# driver.net
KiCad netlist of a schematic drawn in EAGLE
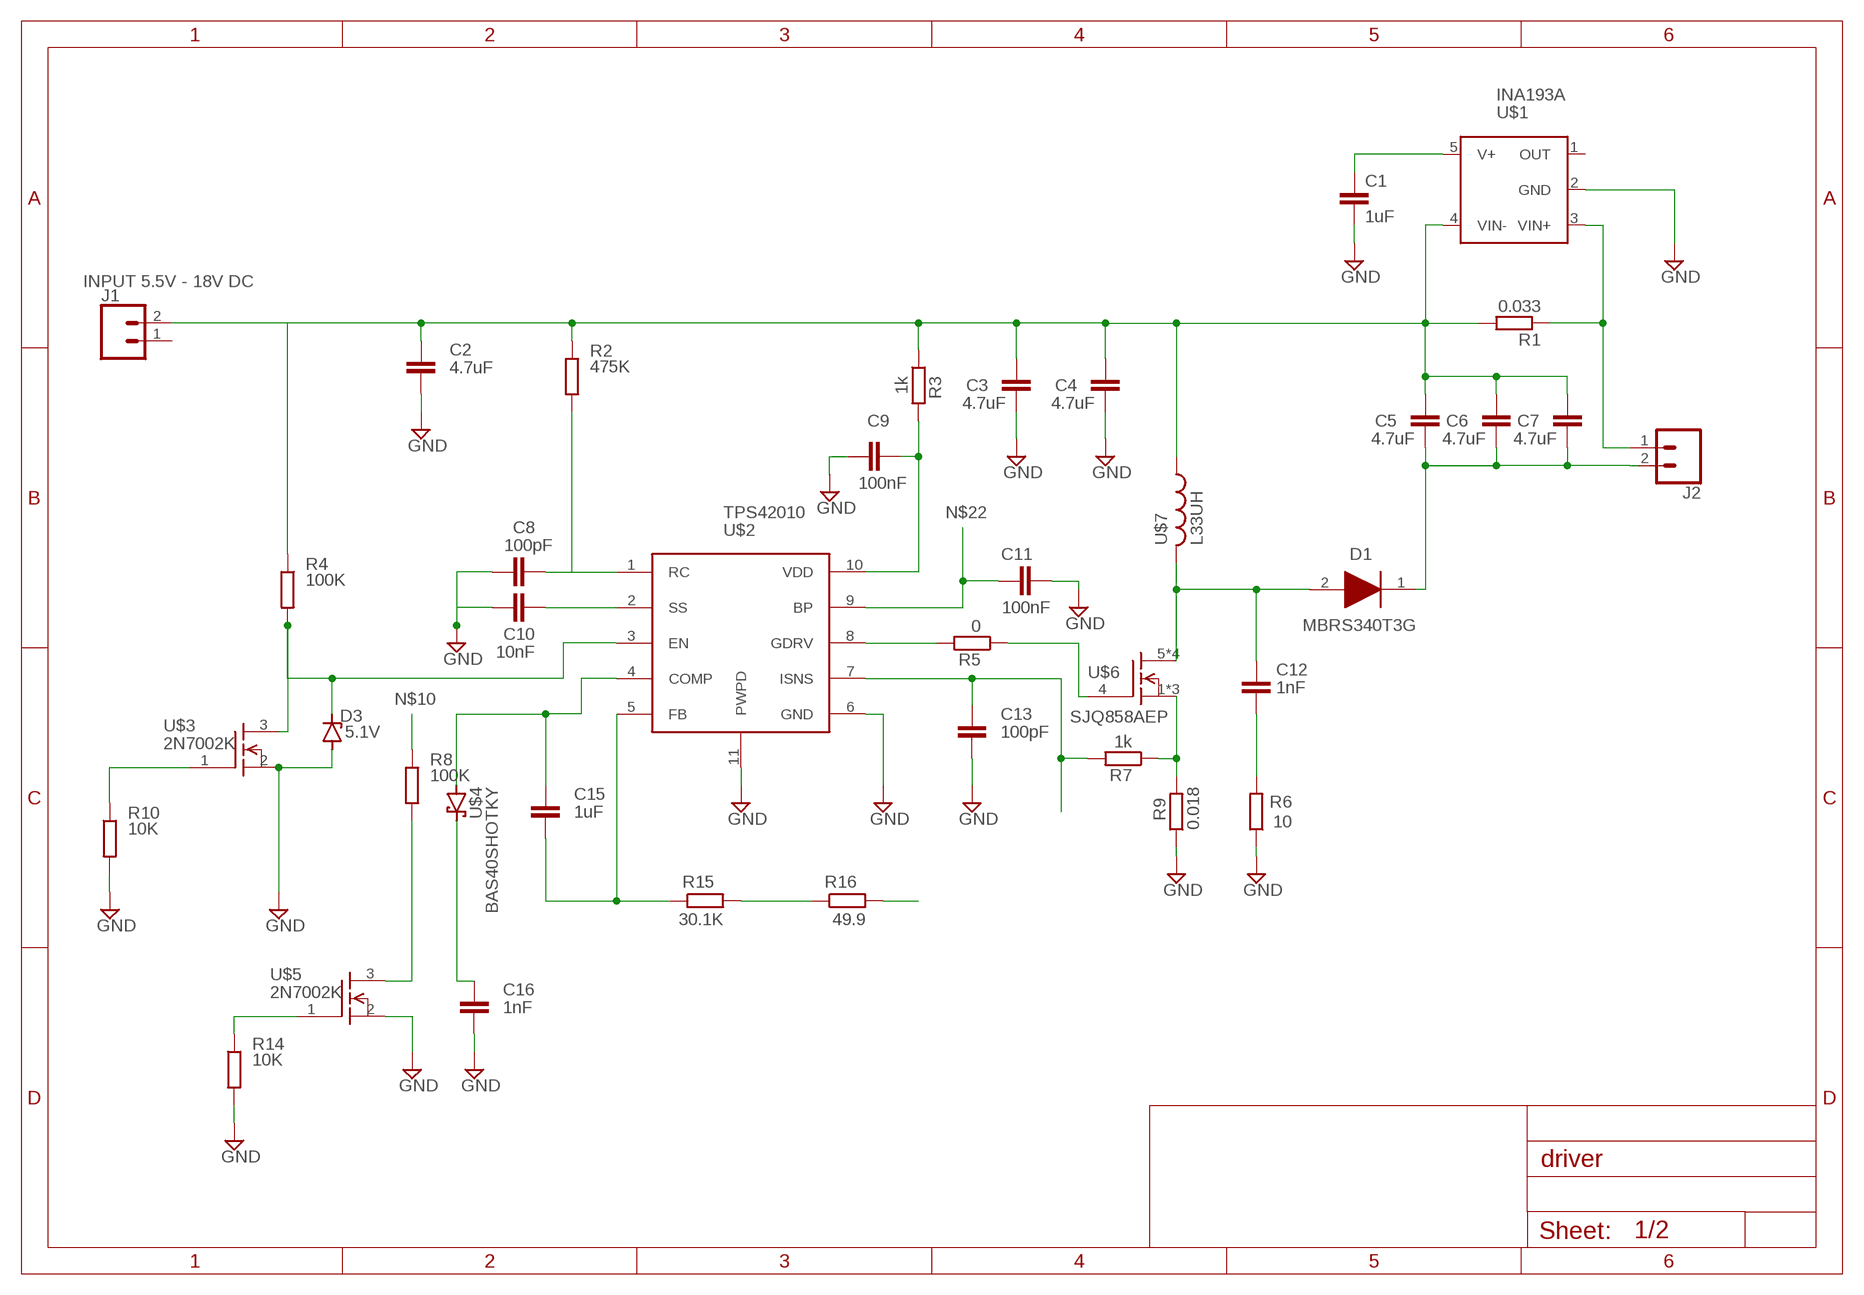
[diagram p0: schematic, sheet 1]
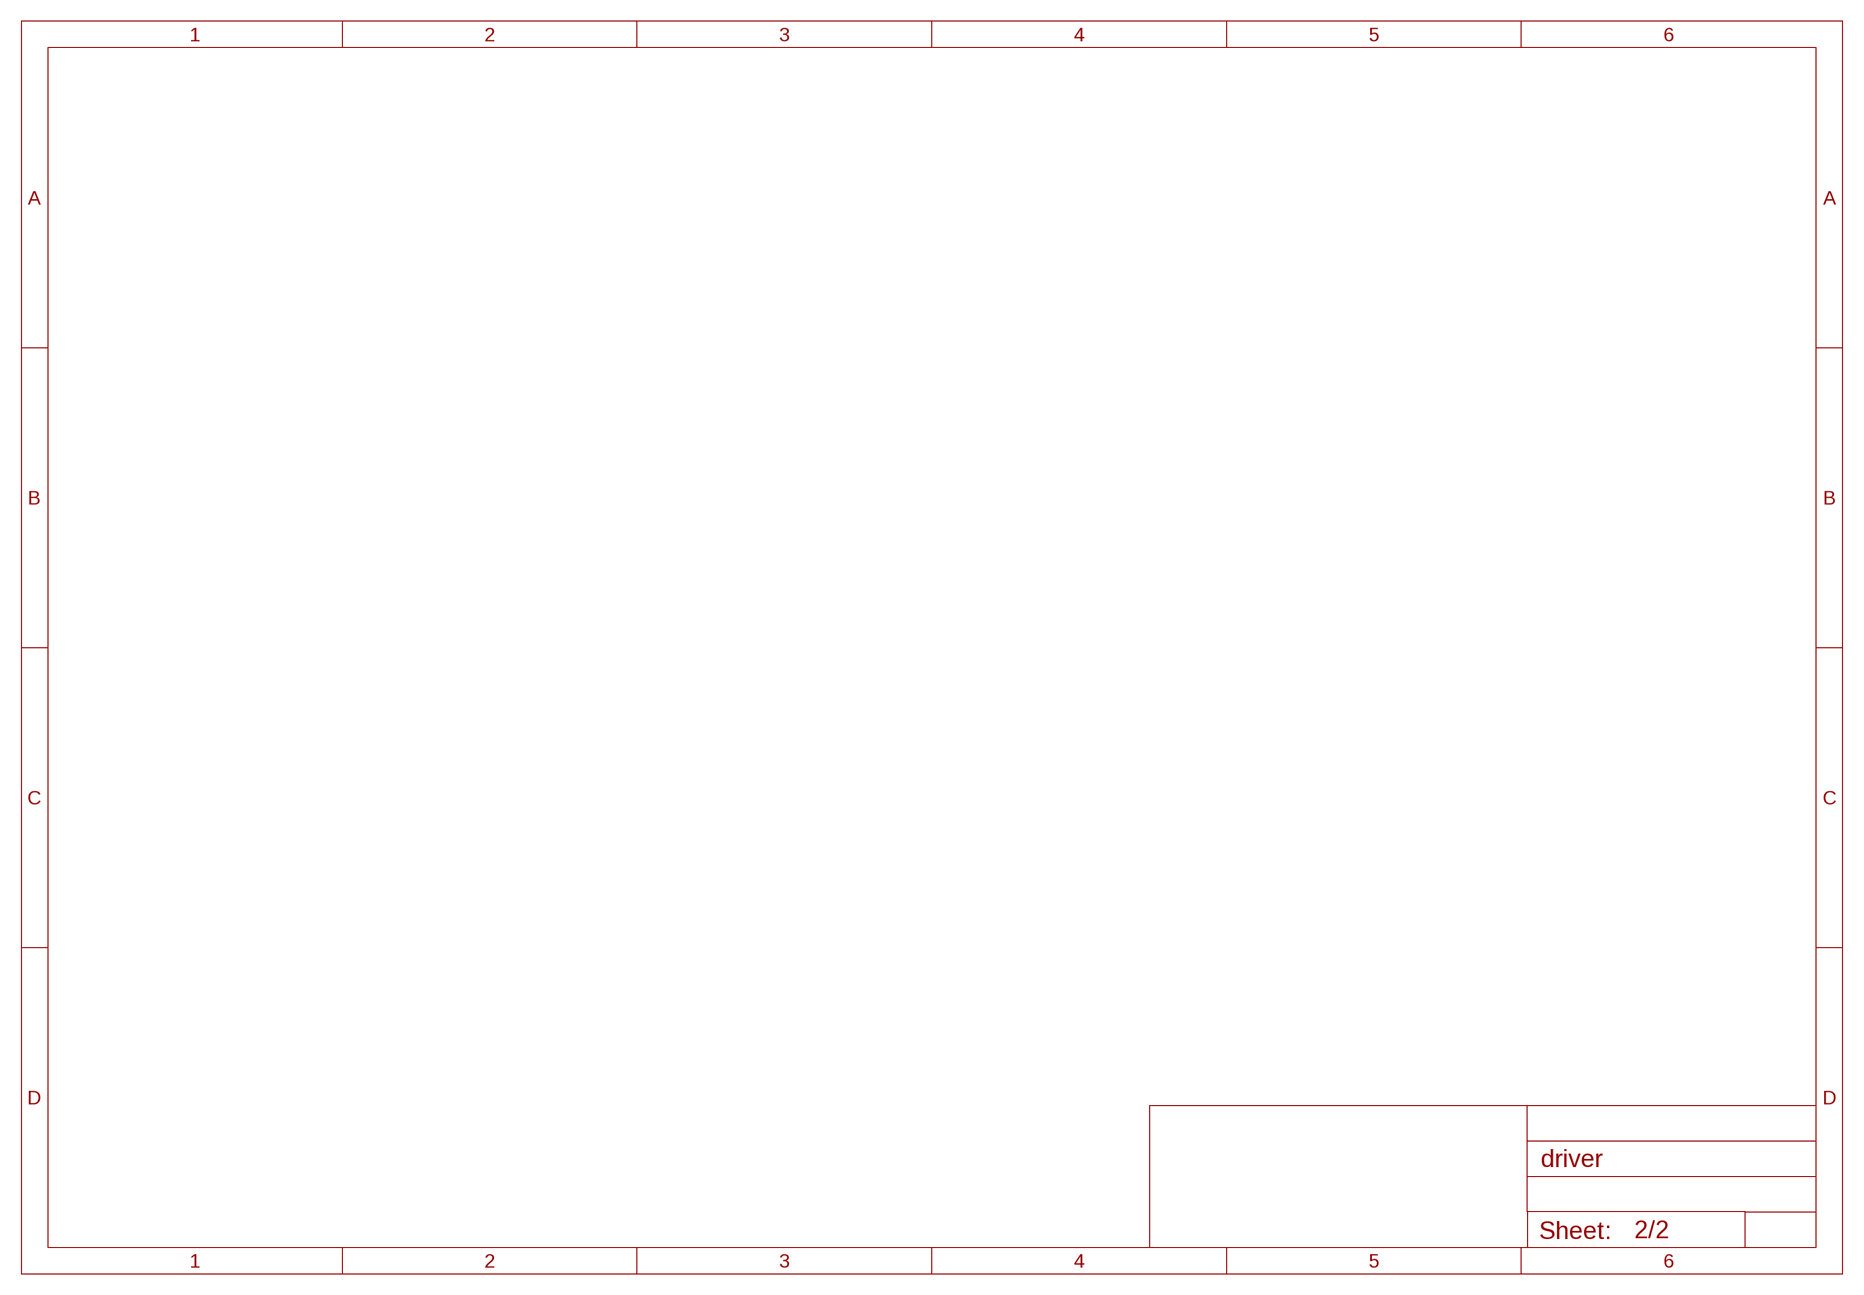
[diagram p1: schematic, sheet 2]

(export (version "E")
  (design (tool "Eeschema 10.0.6"))
  (components
    (comp (ref "C1")
      (value "1uF")
      (footprint "eagle-import:C0603")
      (libsource (lib "eagle-import") (part "C-EUC0603"))
    )
    (comp (ref "C2")
      (value "4.7uF")
      (footprint "eagle-import:C0603")
      (libsource (lib "eagle-import") (part "C-EUC0603"))
    )
    (comp (ref "C3")
      (value "4.7uF")
      (footprint "eagle-import:C0603")
      (libsource (lib "eagle-import") (part "C-EUC0603"))
    )
    (comp (ref "C4")
      (value "4.7uF")
      (footprint "eagle-import:C0603")
      (libsource (lib "eagle-import") (part "C-EUC0603"))
    )
    (comp (ref "C5")
      (value "4.7uF")
      (footprint "eagle-import:C0603")
      (libsource (lib "eagle-import") (part "C-EUC0603"))
    )
    (comp (ref "C6")
      (value "4.7uF")
      (footprint "eagle-import:C0603")
      (libsource (lib "eagle-import") (part "C-EUC0603"))
    )
    (comp (ref "C7")
      (value "4.7uF")
      (footprint "eagle-import:C0603")
      (libsource (lib "eagle-import") (part "C-EUC0603"))
    )
    (comp (ref "C8")
      (value "100pF")
      (footprint "eagle-import:C0603")
      (libsource (lib "eagle-import") (part "C-EUC0603"))
    )
    (comp (ref "C9")
      (value "100nF")
      (footprint "eagle-import:C0603")
      (libsource (lib "eagle-import") (part "C-EUC0603"))
    )
    (comp (ref "C10")
      (value "10nF")
      (footprint "eagle-import:C0603")
      (libsource (lib "eagle-import") (part "C-EUC0603"))
    )
    (comp (ref "C11")
      (value "100nF")
      (footprint "eagle-import:C0603")
      (libsource (lib "eagle-import") (part "C-EUC0603"))
    )
    (comp (ref "C12")
      (value "1nF")
      (footprint "eagle-import:C0603")
      (libsource (lib "eagle-import") (part "C-EUC0603"))
    )
    (comp (ref "C13")
      (value "100pF")
      (footprint "eagle-import:C0603")
      (libsource (lib "eagle-import") (part "C-EUC0603"))
    )
    (comp (ref "C15")
      (value "1uF")
      (footprint "eagle-import:C0603")
      (libsource (lib "eagle-import") (part "C-EUC0603"))
    )
    (comp (ref "C16")
      (value "1nF")
      (footprint "eagle-import:C0603")
      (libsource (lib "eagle-import") (part "C-EUC0603"))
    )
    (comp (ref "D1")
      (value "MBRS340T3G")
      (footprint "eagle-import:DIOM8059X261N")
      (fields (field (name "MOUSER_PART_NUMBER") "863-MBRS340T3G"))
      (libsource (lib "eagle-import") (part "MBRS340T3G"))
    )
    (comp (ref "D3")
      (value "5.1V")
      (footprint "eagle-import:SOT23")
      (libsource (lib "eagle-import") (part "ZENER-DIODESOT23"))
    )
    (comp (ref "J1")
      (value "CONN_02PTH4")
      (footprint "eagle-import:1X02_XTRA_BIG")
      (libsource (lib "eagle-import") (part "CONN_02PTH4"))
    )
    (comp (ref "J2")
      (value "CONN_02PTH4")
      (footprint "eagle-import:1X02_XTRA_BIG")
      (libsource (lib "eagle-import") (part "CONN_02PTH4"))
    )
    (comp (ref "R1")
      (value "0.033")
      (footprint "eagle-import:R0603")
      (libsource (lib "eagle-import") (part "rcl_334_R-EU_R0603"))
    )
    (comp (ref "R2")
      (value "475K")
      (footprint "eagle-import:R0603")
      (libsource (lib "eagle-import") (part "rcl_334_R-EU_R0603"))
    )
    (comp (ref "R3")
      (value "1k")
      (footprint "eagle-import:R0603")
      (libsource (lib "eagle-import") (part "rcl_334_R-EU_R0603"))
    )
    (comp (ref "R4")
      (value "100K")
      (footprint "eagle-import:R0603")
      (libsource (lib "eagle-import") (part "rcl_334_R-EU_R0603"))
    )
    (comp (ref "R5")
      (value "0")
      (footprint "eagle-import:R0603")
      (libsource (lib "eagle-import") (part "rcl_334_R-EU_R0603"))
    )
    (comp (ref "R6")
      (value "10")
      (footprint "eagle-import:R1206")
      (libsource (lib "eagle-import") (part "R-EU_R1206"))
    )
    (comp (ref "R7")
      (value "1k")
      (footprint "eagle-import:R0603")
      (libsource (lib "eagle-import") (part "rcl_334_R-EU_R0603"))
    )
    (comp (ref "R8")
      (value "100K")
      (footprint "eagle-import:R0603")
      (libsource (lib "eagle-import") (part "rcl_334_R-EU_R0603"))
    )
    (comp (ref "R9")
      (value "0.018")
      (footprint "eagle-import:R1206")
      (libsource (lib "eagle-import") (part "R-EU_R1206"))
    )
    (comp (ref "R10")
      (value "10K")
      (footprint "eagle-import:R0603")
      (libsource (lib "eagle-import") (part "rcl_334_R-EU_R0603"))
    )
    (comp (ref "R14")
      (value "10K")
      (footprint "eagle-import:R0603")
      (libsource (lib "eagle-import") (part "rcl_334_R-EU_R0603"))
    )
    (comp (ref "R15")
      (value "30.1K")
      (footprint "eagle-import:R0603")
      (libsource (lib "eagle-import") (part "rcl_334_R-EU_R0603"))
    )
    (comp (ref "R16")
      (value "49.9")
      (footprint "eagle-import:R0603")
      (libsource (lib "eagle-import") (part "rcl_334_R-EU_R0603"))
    )
    (comp (ref "U$1")
      (value "INA193A")
      (footprint "eagle-import:SOT95P280X145-5N")
      (libsource (lib "eagle-import") (part "INA193A"))
    )
    (comp (ref "U$2")
      (value "TPS42010")
      (footprint "eagle-import:SOP50P490X110-11N")
      (libsource (lib "eagle-import") (part "TPS42010"))
    )
    (comp (ref "U$3")
      (value "2N7002K")
      (footprint "eagle-import:SOT95P237X112-3N")
      (libsource (lib "eagle-import") (part "2N7002K"))
    )
    (comp (ref "U$4")
      (value "BAS40SHOTKY")
      (footprint "eagle-import:SOT323-3")
      (libsource (lib "eagle-import") (part "BAS40SHOTKY"))
    )
    (comp (ref "U$5")
      (value "2N7002K")
      (footprint "eagle-import:SOT95P237X112-3N")
      (libsource (lib "eagle-import") (part "2N7002K"))
    )
    (comp (ref "U$6")
      (value "SJQ858AEP")
      (footprint "eagle-import:SQJ858AEPT1_GE3")
      (libsource (lib "eagle-import") (part "SJQ858AEP"))
    )
    (comp (ref "U$7")
      (value "L33UH")
      (footprint "eagle-import:L33UH")
      (libsource (lib "eagle-import") (part "L33UH"))
    )
  )
  (nets
    (net (code "1") (name "GND") (class "Default")
      (node (ref "C1") (pin "2") (pinfunction "2_2") (pintype "passive"))
      (node (ref "C10") (pin "1") (pinfunction "1_1") (pintype "passive"))
      (node (ref "C11") (pin "2") (pinfunction "2_2") (pintype "passive"))
      (node (ref "C13") (pin "2") (pinfunction "2_2") (pintype "passive"))
      (node (ref "C16") (pin "2") (pinfunction "2_2") (pintype "passive"))
      (node (ref "C2") (pin "2") (pinfunction "2_2") (pintype "passive"))
      (node (ref "C3") (pin "2") (pinfunction "2_2") (pintype "passive"))
      (node (ref "C4") (pin "2") (pinfunction "2_2") (pintype "passive"))
      (node (ref "C8") (pin "1") (pinfunction "1_1") (pintype "passive"))
      (node (ref "C9") (pin "2") (pinfunction "2_2") (pintype "passive"))
      (node (ref "D3") (pin "1") (pinfunction "A_1") (pintype "passive"))
      (node (ref "R10") (pin "2") (pinfunction "2_2") (pintype "passive"))
      (node (ref "R14") (pin "2") (pinfunction "2_2") (pintype "passive"))
      (node (ref "R6") (pin "1") (pinfunction "1_1") (pintype "passive"))
      (node (ref "R9") (pin "1") (pinfunction "1_1") (pintype "passive"))
      (node (ref "U$1") (pin "2") (pinfunction "GND_2") (pintype "bidirectional"))
      (node (ref "U$2") (pin "11") (pinfunction "PWPD_11") (pintype "bidirectional"))
      (node (ref "U$2") (pin "6") (pinfunction "GND_6") (pintype "bidirectional"))
      (node (ref "U$3") (pin "2") (pinfunction "S_2") (pintype "bidirectional"))
      (node (ref "U$5") (pin "2") (pinfunction "S_2") (pintype "bidirectional"))
    )
    (net (code "2") (name "N$10") (class "Default")
      (node (ref "R8") (pin "1") (pinfunction "1_1") (pintype "passive"))
    )
    (net (code "3") (name "N$22") (class "Default")
      (node (ref "C11") (pin "1") (pinfunction "1_1") (pintype "passive"))
      (node (ref "U$2") (pin "9") (pinfunction "BP_9") (pintype "bidirectional"))
    )
    (net (code "4") (name "Net-(C12-Pad1)") (class "Default")
      (node (ref "C12") (pin "1") (pinfunction "1_1") (pintype "passive"))
      (node (ref "R6") (pin "2") (pinfunction "2_2") (pintype "passive"))
    )
    (net (code "5") (name "Net-(D1-A)") (class "Default")
      (node (ref "C12") (pin "2") (pinfunction "2_2") (pintype "passive"))
      (node (ref "D1") (pin "2") (pinfunction "A_2") (pintype "bidirectional"))
      (node (ref "U$6") (pin "5") (pinfunction "D_5") (pintype "bidirectional"))
      (node (ref "U$6") (pin "6") (pinfunction "D_6") (pintype "bidirectional"))
      (node (ref "U$6") (pin "7") (pinfunction "D_7") (pintype "bidirectional"))
      (node (ref "U$6") (pin "8") (pinfunction "D_8") (pintype "bidirectional"))
      (node (ref "U$7") (pin "P$2") (pinfunction "2_P$2") (pintype "passive"))
    )
    (net (code "6") (name "Net-(D1-K)") (class "Default")
      (node (ref "C5") (pin "2") (pinfunction "2_2") (pintype "passive"))
      (node (ref "C6") (pin "2") (pinfunction "2_2") (pintype "passive"))
      (node (ref "C7") (pin "2") (pinfunction "2_2") (pintype "passive"))
      (node (ref "D1") (pin "1") (pinfunction "K_1") (pintype "bidirectional"))
      (node (ref "J2") (pin "2") (pinfunction "2_2") (pintype "passive"))
    )
    (net (code "7") (name "Net-(D3-C)") (class "Default")
      (node (ref "D3") (pin "3") (pinfunction "C_3") (pintype "passive"))
      (node (ref "R4") (pin "2") (pinfunction "2_2") (pintype "passive"))
      (node (ref "U$2") (pin "3") (pinfunction "EN_3") (pintype "bidirectional"))
      (node (ref "U$3") (pin "3") (pinfunction "D_3") (pintype "bidirectional"))
    )
    (net (code "8") (name "Net-(R7-Pad1)") (class "Default")
      (node (ref "R7") (pin "1") (pinfunction "1_1") (pintype "passive"))
      (node (ref "R9") (pin "2") (pinfunction "2_2") (pintype "passive"))
      (node (ref "U$6") (pin "1") (pinfunction "S_1") (pintype "bidirectional"))
      (node (ref "U$6") (pin "2") (pinfunction "S_2") (pintype "bidirectional"))
      (node (ref "U$6") (pin "3") (pinfunction "S_3") (pintype "bidirectional"))
    )
    (net (code "9") (name "Net-(R15-Pad2)") (class "Default")
      (node (ref "R15") (pin "2") (pinfunction "2_2") (pintype "passive"))
      (node (ref "R16") (pin "1") (pinfunction "1_1") (pintype "passive"))
    )
    (net (code "10") (name "Net-(U$1-V+)") (class "Default")
      (node (ref "C1") (pin "1") (pinfunction "1_1") (pintype "passive"))
      (node (ref "U$1") (pin "5") (pinfunction "V+_5") (pintype "bidirectional"))
    )
    (net (code "11") (name "Net-(U$1-VIN+)") (class "Default")
      (node (ref "J2") (pin "1") (pinfunction "1_1") (pintype "passive"))
      (node (ref "R1") (pin "1") (pinfunction "1_1") (pintype "passive"))
      (node (ref "U$1") (pin "3") (pinfunction "VIN+_3") (pintype "bidirectional"))
    )
    (net (code "12") (name "Net-(U$1-VIN-)") (class "Default")
      (node (ref "C2") (pin "1") (pinfunction "1_1") (pintype "passive"))
      (node (ref "C3") (pin "1") (pinfunction "1_1") (pintype "passive"))
      (node (ref "C4") (pin "1") (pinfunction "1_1") (pintype "passive"))
      (node (ref "C5") (pin "1") (pinfunction "1_1") (pintype "passive"))
      (node (ref "C6") (pin "1") (pinfunction "1_1") (pintype "passive"))
      (node (ref "C7") (pin "1") (pinfunction "1_1") (pintype "passive"))
      (node (ref "J1") (pin "2") (pinfunction "2_2") (pintype "passive"))
      (node (ref "R1") (pin "2") (pinfunction "2_2") (pintype "passive"))
      (node (ref "R2") (pin "1") (pinfunction "1_1") (pintype "passive"))
      (node (ref "R3") (pin "1") (pinfunction "1_1") (pintype "passive"))
      (node (ref "R4") (pin "1") (pinfunction "1_1") (pintype "passive"))
      (node (ref "U$1") (pin "4") (pinfunction "VIN-_4") (pintype "bidirectional"))
      (node (ref "U$7") (pin "P$1") (pinfunction "1_P$1") (pintype "passive"))
    )
    (net (code "13") (name "Net-(U$2-COMP)") (class "Default")
      (node (ref "C15") (pin "1") (pinfunction "1_1") (pintype "passive"))
      (node (ref "U$2") (pin "4") (pinfunction "COMP_4") (pintype "bidirectional"))
      (node (ref "U$4") (pin "P$1") (pinfunction "A_P$1") (pintype "passive"))
    )
    (net (code "14") (name "Net-(U$2-FB)") (class "Default")
      (node (ref "C15") (pin "2") (pinfunction "2_2") (pintype "passive"))
      (node (ref "R15") (pin "1") (pinfunction "1_1") (pintype "passive"))
      (node (ref "U$2") (pin "5") (pinfunction "FB_5") (pintype "bidirectional"))
    )
    (net (code "15") (name "Net-(U$2-GDRV)") (class "Default")
      (node (ref "R5") (pin "2") (pinfunction "2_2") (pintype "passive"))
      (node (ref "U$2") (pin "8") (pinfunction "GDRV_8") (pintype "bidirectional"))
    )
    (net (code "16") (name "Net-(U$2-ISNS)") (class "Default")
      (node (ref "C13") (pin "1") (pinfunction "1_1") (pintype "passive"))
      (node (ref "R7") (pin "2") (pinfunction "2_2") (pintype "passive"))
      (node (ref "U$2") (pin "7") (pinfunction "ISNS_7") (pintype "bidirectional"))
    )
    (net (code "17") (name "Net-(U$2-RC)") (class "Default")
      (node (ref "C8") (pin "2") (pinfunction "2_2") (pintype "passive"))
      (node (ref "R2") (pin "2") (pinfunction "2_2") (pintype "passive"))
      (node (ref "U$2") (pin "1") (pinfunction "RC_1") (pintype "bidirectional"))
    )
    (net (code "18") (name "Net-(U$2-SS)") (class "Default")
      (node (ref "C10") (pin "2") (pinfunction "2_2") (pintype "passive"))
      (node (ref "U$2") (pin "2") (pinfunction "SS_2") (pintype "bidirectional"))
    )
    (net (code "19") (name "Net-(U$2-VDD)") (class "Default")
      (node (ref "C9") (pin "1") (pinfunction "1_1") (pintype "passive"))
      (node (ref "R3") (pin "2") (pinfunction "2_2") (pintype "passive"))
      (node (ref "U$2") (pin "10") (pinfunction "VDD_10") (pintype "bidirectional"))
    )
    (net (code "20") (name "Net-(U$3-G)") (class "Default")
      (node (ref "R10") (pin "1") (pinfunction "1_1") (pintype "passive"))
      (node (ref "U$3") (pin "1") (pinfunction "G_1") (pintype "bidirectional"))
    )
    (net (code "21") (name "Net-(U$4-C)") (class "Default")
      (node (ref "C16") (pin "1") (pinfunction "1_1") (pintype "passive"))
      (node (ref "U$4") (pin "P$3") (pinfunction "C_P$3") (pintype "passive"))
    )
    (net (code "22") (name "Net-(U$5-D)") (class "Default")
      (node (ref "R8") (pin "2") (pinfunction "2_2") (pintype "passive"))
      (node (ref "U$5") (pin "3") (pinfunction "D_3") (pintype "bidirectional"))
    )
    (net (code "23") (name "Net-(U$5-G)") (class "Default")
      (node (ref "R14") (pin "1") (pinfunction "1_1") (pintype "passive"))
      (node (ref "U$5") (pin "1") (pinfunction "G_1") (pintype "bidirectional"))
    )
    (net (code "24") (name "Net-(U$6-G)") (class "Default")
      (node (ref "R5") (pin "1") (pinfunction "1_1") (pintype "passive"))
      (node (ref "U$6") (pin "4") (pinfunction "G_4") (pintype "bidirectional"))
    )
    (net (code "25") (name "unconnected-(J1-Pad1)") (class "Default")
      (node (ref "J1") (pin "1") (pinfunction "1_1") (pintype "passive"))
    )
    (net (code "26") (name "unconnected-(R16-Pad2)") (class "Default")
      (node (ref "R16") (pin "2") (pinfunction "2_2") (pintype "passive"))
    )
    (net (code "27") (name "unconnected-(U$1-OUT-Pad1)") (class "Default")
      (node (ref "U$1") (pin "1") (pinfunction "OUT_1") (pintype "bidirectional"))
    )
  )
)
